# Port.net
KiCad netlist of a schematic drawn in Altium Designer
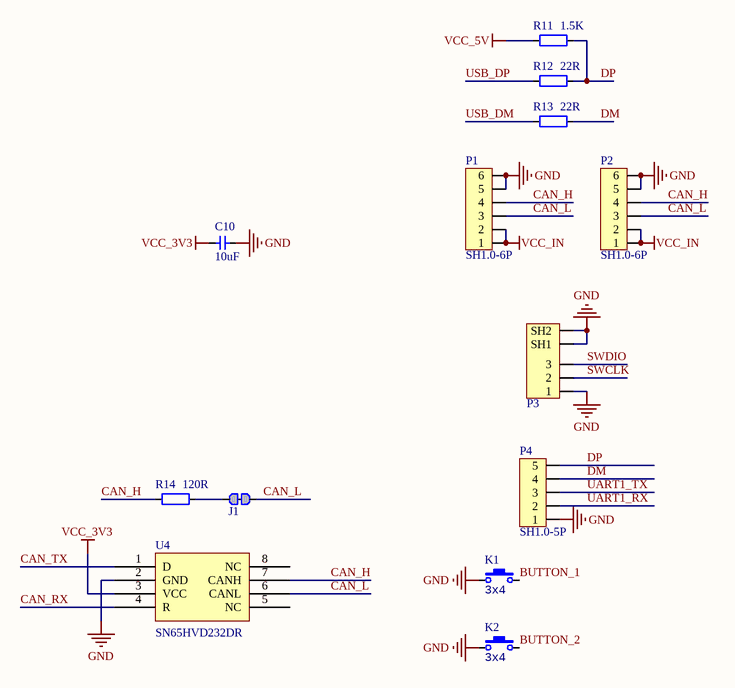
[diagram p0: Port.SchDoc]

(export (version "E")
  (design (tool "Eeschema 10.0.6"))
  (components
    (comp (ref "C10")
      (value "10uF")
      (footprint "CAP_0402")
      (description "Capacitor")
      (libsource (lib "MyPcbLib") (part "电容-0402"))
    )
    (comp (ref "J1")
      (value "跳线")
      (footprint "0402-0R")
      (description "Resistor")
      (fields (field (name "PUBLISHER") "Altium Limited"))
      (libsource (lib "MyPcbLib") (part "跳线"))
    )
    (comp (ref "K1")
      (value "3x4")
      (footprint "ButtonTACT_3x4x2_180")
      (description "Button")
      (fields (field (name "Comment") "TACT 2P"))
      (libsource (lib "KitSprout") (part "ButtonTACT_3x4x2_180"))
    )
    (comp (ref "K2")
      (value "3x4")
      (footprint "ButtonTACT_3x4x2_180")
      (description "Button")
      (fields (field (name "Comment") "TACT 2P"))
      (libsource (lib "KitSprout") (part "ButtonTACT_3x4x2_180"))
    )
    (comp (ref "P1") (value "SH1.0-6P") (footprint "SH1.0-6P") (libsource (lib "MyPcbLib") (part "SH1.0-6P")))
    (comp (ref "P2") (value "SH1.0-6P") (footprint "SH1.0-6P") (libsource (lib "MyPcbLib") (part "SH1.0-6P")))
    (comp (ref "P3")
      (value "SH1.0-3P")
      (footprint "SH1.0-3P")
      (description "Header")
      (libsource (lib "MyPcbLib") (part "SH1.0-3P"))
    )
    (comp (ref "P4") (value "SH1.0-5P") (footprint "SH1.0-5P") (libsource (lib "MyPcbLib") (part "SH1.0-5P")))
    (comp (ref "R11")
      (value "1.5K")
      (footprint "RES_0402")
      (description "Resistor")
      (libsource (lib "MyPcbLib") (part "电阻-0402"))
    )
    (comp (ref "R12")
      (value "22R")
      (footprint "RES_0402")
      (description "Resistor")
      (libsource (lib "MyPcbLib") (part "电阻-0402"))
    )
    (comp (ref "R13")
      (value "22R")
      (footprint "RES_0402")
      (description "Resistor")
      (libsource (lib "MyPcbLib") (part "电阻-0402"))
    )
    (comp (ref "R14")
      (value "120R")
      (footprint "RES_0402")
      (description "Resistor")
      (libsource (lib "MyPcbLib") (part "电阻-0402"))
    )
    (comp (ref "U4")
      (value "SN65HVD232D")
      (footprint "SO-8")
      (fields
        (field (name "MANUFACTURER") "Texas Instruments")
        (field (name "MANUFACTURER PART NUMBER") "SN65HVD232DR")
      )
      (libsource (lib "MyPcbLib") (part "SN65HVD232D"))
    )
  )
  (nets
    (net (code "1") (name "/BUTTON_1") (class "Default")
      (node (ref "K1") (pin "2") (pinfunction "2_2") (pintype "passive"))
    )
    (net (code "2") (name "/BUTTON_2") (class "Default")
      (node (ref "K2") (pin "2") (pinfunction "2_2") (pintype "passive"))
    )
    (net (code "3") (name "/CAN_H") (class "Default")
      (node (ref "P1") (pin "4") (pinfunction "4_4") (pintype "passive"))
      (node (ref "P2") (pin "4") (pinfunction "4_4") (pintype "passive"))
      (node (ref "R14") (pin "1") (pinfunction "1_1") (pintype "passive"))
      (node (ref "U4") (pin "7") (pinfunction "CANH_7") (pintype "passive"))
    )
    (net (code "4") (name "/CAN_L") (class "Default")
      (node (ref "J1") (pin "2") (pinfunction "2_2") (pintype "passive"))
      (node (ref "P1") (pin "3") (pinfunction "3_3") (pintype "passive"))
      (node (ref "P2") (pin "3") (pinfunction "3_3") (pintype "passive"))
      (node (ref "U4") (pin "6") (pinfunction "CANL_6") (pintype "passive"))
    )
    (net (code "5") (name "/CAN_RX") (class "Default")
      (node (ref "U4") (pin "4") (pinfunction "R_4") (pintype "passive"))
    )
    (net (code "6") (name "/CAN_TX") (class "Default")
      (node (ref "U4") (pin "1") (pinfunction "D_1") (pintype "passive"))
    )
    (net (code "7") (name "/DM") (class "Default")
      (node (ref "P4") (pin "4") (pinfunction "4_4") (pintype "passive"))
      (node (ref "R13") (pin "2") (pinfunction "2_2") (pintype "passive"))
    )
    (net (code "8") (name "/DP") (class "Default")
      (node (ref "P4") (pin "5") (pinfunction "5_5") (pintype "passive"))
      (node (ref "R11") (pin "2") (pinfunction "2_2") (pintype "passive"))
      (node (ref "R12") (pin "2") (pinfunction "2_2") (pintype "passive"))
    )
    (net (code "9") (name "/SWCLK") (class "Default")
      (node (ref "P3") (pin "2") (pinfunction "2_2") (pintype "passive"))
    )
    (net (code "10") (name "/SWDIO") (class "Default")
      (node (ref "P3") (pin "3") (pinfunction "3_3") (pintype "passive"))
    )
    (net (code "11") (name "/UART1_RX") (class "Default")
      (node (ref "P4") (pin "2") (pinfunction "2_2") (pintype "passive"))
    )
    (net (code "12") (name "/UART1_TX") (class "Default")
      (node (ref "P4") (pin "3") (pinfunction "3_3") (pintype "passive"))
    )
    (net (code "13") (name "/USB_DM") (class "Default")
      (node (ref "R13") (pin "1") (pinfunction "1_1") (pintype "passive"))
    )
    (net (code "14") (name "/USB_DP") (class "Default")
      (node (ref "R12") (pin "1") (pinfunction "1_1") (pintype "passive"))
    )
    (net (code "15") (name "GND") (class "Default")
      (node (ref "C10") (pin "1") (pinfunction "1_1") (pintype "passive"))
      (node (ref "K1") (pin "1") (pinfunction "1_1") (pintype "passive"))
      (node (ref "K2") (pin "1") (pinfunction "1_1") (pintype "passive"))
      (node (ref "P1") (pin "5") (pinfunction "5_5") (pintype "passive"))
      (node (ref "P1") (pin "6") (pinfunction "6_6") (pintype "passive"))
      (node (ref "P2") (pin "5") (pinfunction "5_5") (pintype "passive"))
      (node (ref "P2") (pin "6") (pinfunction "6_6") (pintype "passive"))
      (node (ref "P3") (pin "1") (pinfunction "1_1") (pintype "passive"))
      (node (ref "P3") (pin "SH1") (pinfunction "SH1_SH1") (pintype "passive"))
      (node (ref "P3") (pin "SH2") (pinfunction "SH2_SH2") (pintype "passive"))
      (node (ref "P4") (pin "1") (pinfunction "1_1") (pintype "passive"))
      (node (ref "U4") (pin "2") (pinfunction "GND_2") (pintype "passive"))
    )
    (net (code "16") (name "Net-(J1-Pad1)") (class "Default")
      (node (ref "J1") (pin "1") (pinfunction "1_1") (pintype "passive"))
      (node (ref "R14") (pin "2") (pinfunction "2_2") (pintype "passive"))
    )
    (net (code "17") (name "VCC_3V3") (class "Default")
      (node (ref "C10") (pin "2") (pinfunction "2_2") (pintype "passive"))
      (node (ref "U4") (pin "3") (pinfunction "VCC_3") (pintype "passive"))
    )
    (net (code "18") (name "VCC_5V") (class "Default")
      (node (ref "R11") (pin "1") (pinfunction "1_1") (pintype "passive"))
    )
    (net (code "19") (name "VCC_IN") (class "Default")
      (node (ref "P1") (pin "1") (pinfunction "1_1") (pintype "passive"))
      (node (ref "P1") (pin "2") (pinfunction "2_2") (pintype "passive"))
      (node (ref "P2") (pin "1") (pinfunction "1_1") (pintype "passive"))
      (node (ref "P2") (pin "2") (pinfunction "2_2") (pintype "passive"))
    )
    (net (code "20") (name "unconnected-(U4-NC-Pad5)") (class "Default")
      (node (ref "U4") (pin "5") (pinfunction "NC_5") (pintype "passive"))
    )
    (net (code "21") (name "unconnected-(U4-NC-Pad8)") (class "Default")
      (node (ref "U4") (pin "8") (pinfunction "NC_8") (pintype "passive"))
    )
  )
)
